# TestNode_V1-pan.net
KiCad netlist of a schematic drawn in EAGLE
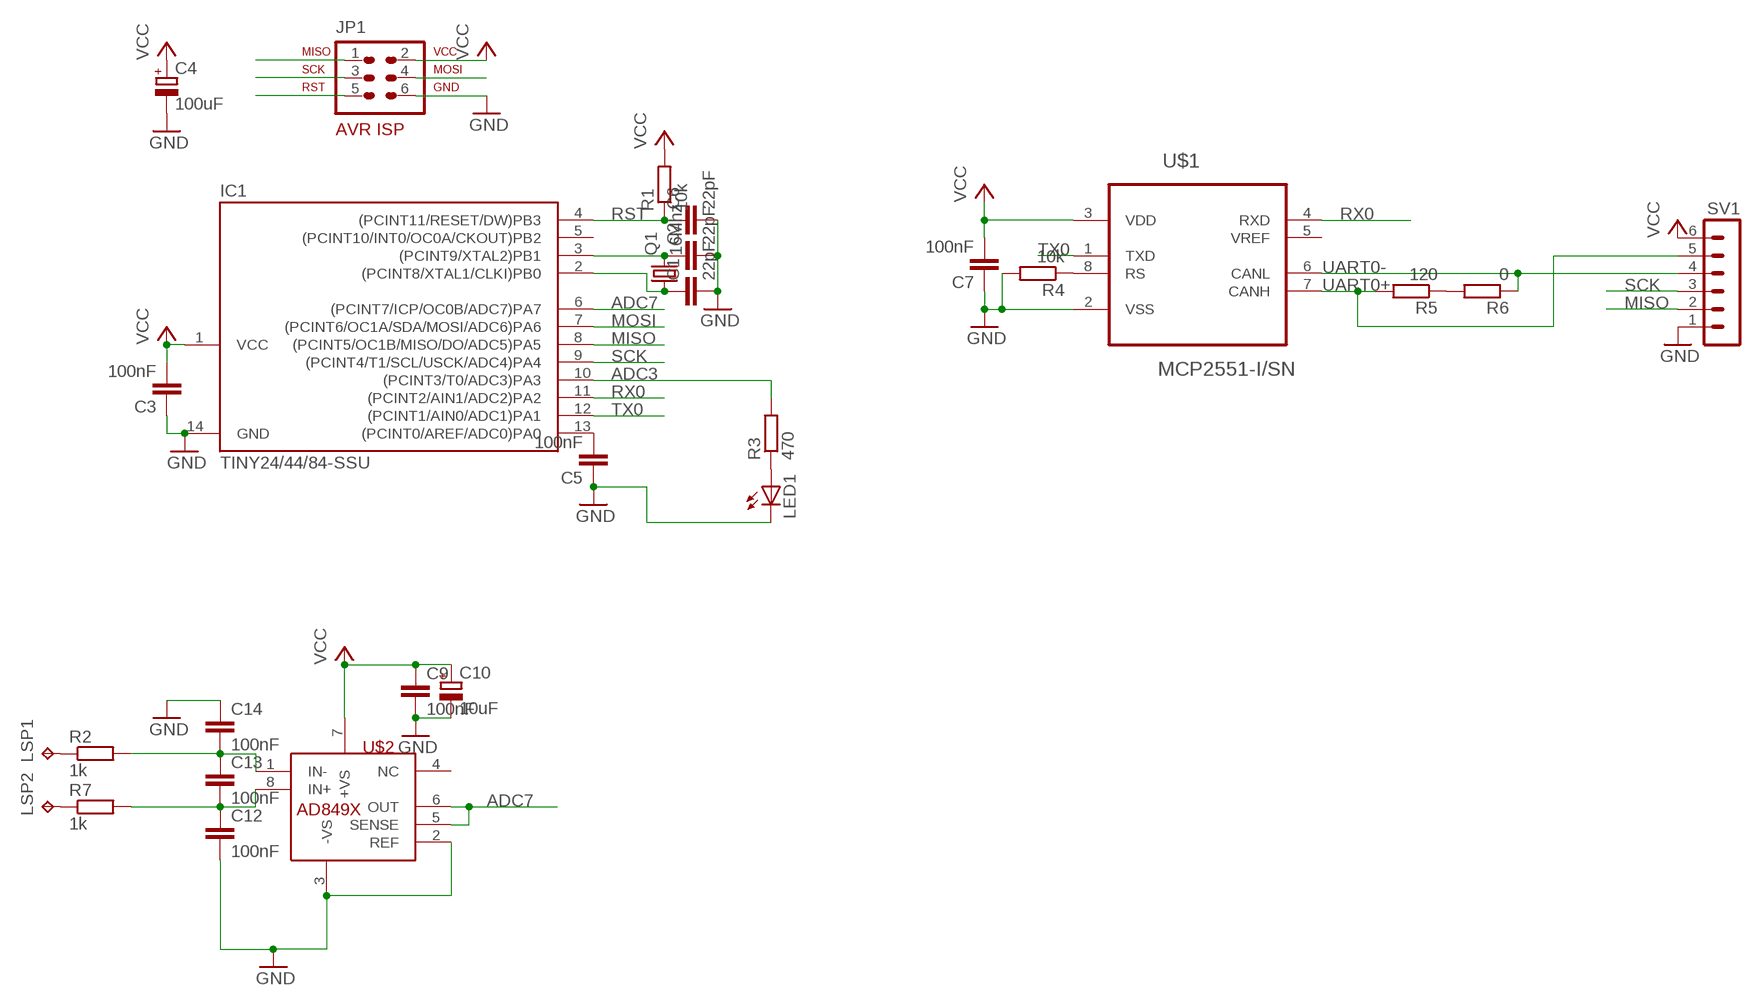
[diagram p0: schematic, sheet 1]

(export (version "E")
  (design (tool "Eeschema 10.0.6"))
  (components
    (comp (ref "C1")
      (value "22pF")
      (footprint "eagle-import:C1206")
      (libsource (lib "eagle-import") (part "C-EUC1206"))
    )
    (comp (ref "C2")
      (value "22pF")
      (footprint "eagle-import:C1206")
      (libsource (lib "eagle-import") (part "C-EUC1206"))
    )
    (comp (ref "C3")
      (value "100nF")
      (footprint "eagle-import:C1206")
      (libsource (lib "eagle-import") (part "C-EUC1206"))
    )
    (comp (ref "C4")
      (value "100uF")
      (footprint "eagle-import:PANASONIC_D")
      (libsource (lib "eagle-import") (part "CPOL-EUD"))
    )
    (comp (ref "C5")
      (value "100nF")
      (footprint "eagle-import:C1206")
      (libsource (lib "eagle-import") (part "C-EUC1206"))
    )
    (comp (ref "C6")
      (value "22pF")
      (footprint "eagle-import:C1206")
      (libsource (lib "eagle-import") (part "C-EUC1206"))
    )
    (comp (ref "C7")
      (value "100nF")
      (footprint "eagle-import:C1206")
      (libsource (lib "eagle-import") (part "C-EUC1206"))
    )
    (comp (ref "C9")
      (value "100nF")
      (footprint "eagle-import:C1206")
      (libsource (lib "eagle-import") (part "C-EUC1206"))
    )
    (comp (ref "C10")
      (value "10uF")
      (footprint "eagle-import:UD-4X5,8_NICHICON")
      (libsource (lib "eagle-import") (part "CPOL-EUUD-4X5,8"))
    )
    (comp (ref "C12")
      (value "100nF")
      (footprint "eagle-import:C0805")
      (libsource (lib "eagle-import") (part "C-EUC0805"))
    )
    (comp (ref "C13")
      (value "100nF")
      (footprint "eagle-import:C0805")
      (libsource (lib "eagle-import") (part "C-EUC0805"))
    )
    (comp (ref "C14")
      (value "100nF")
      (footprint "eagle-import:C0805")
      (libsource (lib "eagle-import") (part "C-EUC0805"))
    )
    (comp (ref "IC1")
      (value "TINY24/44/84-SSU")
      (footprint "eagle-import:SOIC14")
      (libsource (lib "eagle-import") (part "TINY24/44/84-SSU"))
    )
    (comp (ref "JP1")
      (value "AVR-ISP-6VERT")
      (footprint "eagle-import:AVR-ISP-6")
      (libsource (lib "eagle-import") (part "AVR-ISP-6VERT"))
    )
    (comp (ref "LED1")
      (value "LED5MM")
      (footprint "eagle-import:LED5MM")
      (libsource (lib "eagle-import") (part "LED5MM"))
    )
    (comp (ref "LSP1")
      (value "TPTP15R")
      (footprint "eagle-import:TP15R")
      (libsource (lib "eagle-import") (part "TPTP15R"))
    )
    (comp (ref "LSP2")
      (value "TPTP15R")
      (footprint "eagle-import:TP15R")
      (libsource (lib "eagle-import") (part "TPTP15R"))
    )
    (comp (ref "Q1")
      (value "16Mhz")
      (footprint "eagle-import:SM49")
      (libsource (lib "eagle-import") (part "CRYSTALSM49"))
    )
    (comp (ref "R1")
      (value "10k")
      (footprint "eagle-import:R1206")
      (libsource (lib "eagle-import") (part "R-EU_R1206"))
    )
    (comp (ref "R2")
      (value "1k")
      (footprint "eagle-import:R0805")
      (libsource (lib "eagle-import") (part "R-EU_R0805"))
    )
    (comp (ref "R3")
      (value "470")
      (footprint "eagle-import:R1206")
      (libsource (lib "eagle-import") (part "R-EU_R1206"))
    )
    (comp (ref "R4")
      (value "10k")
      (footprint "eagle-import:R1206")
      (libsource (lib "eagle-import") (part "R-EU_R1206"))
    )
    (comp (ref "R5")
      (value "120")
      (footprint "eagle-import:R1206")
      (libsource (lib "eagle-import") (part "R-EU_R1206"))
    )
    (comp (ref "R6")
      (value "0")
      (footprint "eagle-import:R1206")
      (libsource (lib "eagle-import") (part "R-EU_R1206"))
    )
    (comp (ref "R7")
      (value "1k")
      (footprint "eagle-import:R0805")
      (libsource (lib "eagle-import") (part "R-EU_R0805"))
    )
    (comp (ref "SV1")
      (value "MA06-1")
      (footprint "eagle-import:MA06-1")
      (libsource (lib "eagle-import") (part "MA06-1"))
    )
    (comp (ref "U$1")
      (value "MCP2551-I/SN")
      (footprint "eagle-import:SOIC127P600X175-8N")
      (libsource (lib "eagle-import") (part "MCP2551-I/SN"))
    )
    (comp (ref "U$2")
      (value "AD849X")
      (footprint "eagle-import:MSOP8")
      (libsource (lib "eagle-import") (part "AD849X"))
    )
  )
  (nets
    (net (code "1") (name "/ADC3") (class "Default")
      (node (ref "IC1") (pin "10") (pinfunction "(PCINT3/T0/ADC3)PA3_10") (pintype "bidirectional"))
      (node (ref "R3") (pin "2") (pinfunction "2_2") (pintype "passive"))
    )
    (net (code "2") (name "/ADC7") (class "Default")
      (node (ref "IC1") (pin "6") (pinfunction "(PCINT7/ICP/OC0B/ADC7)PA7_6") (pintype "bidirectional"))
      (node (ref "U$2") (pin "5") (pinfunction "SENSE_5") (pintype "input"))
      (node (ref "U$2") (pin "6") (pinfunction "OUT_6") (pintype "output"))
    )
    (net (code "3") (name "/MISO") (class "Default")
      (node (ref "IC1") (pin "8") (pinfunction "(PCINT5/OC1B/MISO/DO/ADC5)PA5_8") (pintype "bidirectional"))
      (node (ref "JP1") (pin "1") (pinfunction "1_1") (pintype "passive"))
      (node (ref "SV1") (pin "2") (pinfunction "2_2") (pintype "passive"))
    )
    (net (code "4") (name "/MOSI") (class "Default")
      (node (ref "IC1") (pin "7") (pinfunction "(PCINT6/OC1A/SDA/MOSI/ADC6)PA6_7") (pintype "bidirectional"))
      (node (ref "JP1") (pin "4") (pinfunction "4_4") (pintype "passive"))
    )
    (net (code "5") (name "/RST") (class "Default")
      (node (ref "C6") (pin "1") (pinfunction "1_1") (pintype "passive"))
      (node (ref "IC1") (pin "4") (pinfunction "(PCINT11/RESET/DW)PB3_4") (pintype "bidirectional"))
      (node (ref "JP1") (pin "5") (pinfunction "5_5") (pintype "passive"))
      (node (ref "R1") (pin "1") (pinfunction "1_1") (pintype "passive"))
    )
    (net (code "6") (name "/RX0") (class "Default")
      (node (ref "IC1") (pin "11") (pinfunction "(PCINT2/AIN1/ADC2)PA2_11") (pintype "bidirectional"))
      (node (ref "U$1") (pin "4") (pinfunction "RXD_4") (pintype "output"))
    )
    (net (code "7") (name "/SCK") (class "Default")
      (node (ref "IC1") (pin "9") (pinfunction "(PCINT4/T1/SCL/USCK/ADC4)PA4_9") (pintype "bidirectional"))
      (node (ref "JP1") (pin "3") (pinfunction "3_3") (pintype "passive"))
      (node (ref "SV1") (pin "3") (pinfunction "3_3") (pintype "passive"))
    )
    (net (code "8") (name "/TX0") (class "Default")
      (node (ref "IC1") (pin "12") (pinfunction "(PCINT1/AIN0/ADC1)PA1_12") (pintype "bidirectional"))
      (node (ref "U$1") (pin "1") (pinfunction "TXD_1") (pintype "input"))
    )
    (net (code "9") (name "/UART0+") (class "Default")
      (node (ref "R5") (pin "2") (pinfunction "2_2") (pintype "passive"))
      (node (ref "SV1") (pin "5") (pinfunction "5_5") (pintype "passive"))
      (node (ref "U$1") (pin "7") (pinfunction "CANH_7") (pintype "bidirectional"))
    )
    (net (code "10") (name "/UART0-") (class "Default")
      (node (ref "R6") (pin "1") (pinfunction "1_1") (pintype "passive"))
      (node (ref "SV1") (pin "4") (pinfunction "4_4") (pintype "passive"))
      (node (ref "U$1") (pin "6") (pinfunction "CANL_6") (pintype "bidirectional"))
    )
    (net (code "11") (name "GND") (class "Default")
      (node (ref "C1") (pin "2") (pinfunction "2_2") (pintype "passive"))
      (node (ref "C10") (pin "-") (pinfunction "-_-") (pintype "passive"))
      (node (ref "C12") (pin "2") (pinfunction "2_2") (pintype "passive"))
      (node (ref "C14") (pin "1") (pinfunction "1_1") (pintype "passive"))
      (node (ref "C2") (pin "2") (pinfunction "2_2") (pintype "passive"))
      (node (ref "C3") (pin "1") (pinfunction "1_1") (pintype "passive"))
      (node (ref "C4") (pin "-") (pinfunction "-_-") (pintype "passive"))
      (node (ref "C5") (pin "1") (pinfunction "1_1") (pintype "passive"))
      (node (ref "C6") (pin "2") (pinfunction "2_2") (pintype "passive"))
      (node (ref "C7") (pin "1") (pinfunction "1_1") (pintype "passive"))
      (node (ref "C9") (pin "2") (pinfunction "2_2") (pintype "passive"))
      (node (ref "IC1") (pin "14") (pinfunction "GND_14") (pintype "power_in"))
      (node (ref "JP1") (pin "6") (pinfunction "6_6") (pintype "passive"))
      (node (ref "LED1") (pin "K") (pinfunction "C_K") (pintype "passive"))
      (node (ref "R4") (pin "2") (pinfunction "2_2") (pintype "passive"))
      (node (ref "SV1") (pin "1") (pinfunction "1_1") (pintype "passive"))
      (node (ref "U$1") (pin "2") (pinfunction "VSS_2") (pintype "passive"))
      (node (ref "U$2") (pin "2") (pinfunction "REF_2") (pintype "input"))
      (node (ref "U$2") (pin "3") (pinfunction "-VS_3") (pintype "power_in"))
    )
    (net (code "12") (name "Net-(IC1-(PCINT0{slash}AREF{slash}ADC0)PA0)") (class "Default")
      (node (ref "C5") (pin "2") (pinfunction "2_2") (pintype "passive"))
      (node (ref "IC1") (pin "13") (pinfunction "(PCINT0/AREF/ADC0)PA0_13") (pintype "bidirectional"))
    )
    (net (code "13") (name "Net-(IC1-(PCINT8{slash}XTAL1{slash}CLKI)PB0)") (class "Default")
      (node (ref "C1") (pin "1") (pinfunction "1_1") (pintype "passive"))
      (node (ref "IC1") (pin "2") (pinfunction "(PCINT8/XTAL1/CLKI)PB0_2") (pintype "bidirectional"))
      (node (ref "Q1") (pin "1") (pinfunction "1_1") (pintype "passive"))
    )
    (net (code "14") (name "Net-(IC1-(PCINT9{slash}XTAL2)PB1)") (class "Default")
      (node (ref "C2") (pin "1") (pinfunction "1_1") (pintype "passive"))
      (node (ref "IC1") (pin "3") (pinfunction "(PCINT9/XTAL2)PB1_3") (pintype "bidirectional"))
      (node (ref "Q1") (pin "2") (pinfunction "2_2") (pintype "passive"))
    )
    (net (code "15") (name "Net-(LED1-PadA)") (class "Default")
      (node (ref "LED1") (pin "A") (pinfunction "A_A") (pintype "passive"))
      (node (ref "R3") (pin "1") (pinfunction "1_1") (pintype "passive"))
    )
    (net (code "16") (name "Net-(LSP1-PadTP)") (class "Default")
      (node (ref "LSP1") (pin "TP") (pinfunction "TP_TP") (pintype "input"))
      (node (ref "R2") (pin "1") (pinfunction "1_1") (pintype "passive"))
    )
    (net (code "17") (name "Net-(LSP2-PadTP)") (class "Default")
      (node (ref "LSP2") (pin "TP") (pinfunction "TP_TP") (pintype "input"))
      (node (ref "R7") (pin "1") (pinfunction "1_1") (pintype "passive"))
    )
    (net (code "18") (name "Net-(R5-Pad1)") (class "Default")
      (node (ref "R5") (pin "1") (pinfunction "1_1") (pintype "passive"))
      (node (ref "R6") (pin "2") (pinfunction "2_2") (pintype "passive"))
    )
    (net (code "19") (name "Net-(U$1-RS)") (class "Default")
      (node (ref "R4") (pin "1") (pinfunction "1_1") (pintype "passive"))
      (node (ref "U$1") (pin "8") (pinfunction "RS_8") (pintype "input"))
    )
    (net (code "20") (name "Net-(U$2-IN+)") (class "Default")
      (node (ref "C12") (pin "1") (pinfunction "1_1") (pintype "passive"))
      (node (ref "C13") (pin "2") (pinfunction "2_2") (pintype "passive"))
      (node (ref "R7") (pin "2") (pinfunction "2_2") (pintype "passive"))
      (node (ref "U$2") (pin "8") (pinfunction "IN+_8") (pintype "input"))
    )
    (net (code "21") (name "Net-(U$2-IN-)") (class "Default")
      (node (ref "C13") (pin "1") (pinfunction "1_1") (pintype "passive"))
      (node (ref "C14") (pin "2") (pinfunction "2_2") (pintype "passive"))
      (node (ref "R2") (pin "2") (pinfunction "2_2") (pintype "passive"))
      (node (ref "U$2") (pin "1") (pinfunction "IN-_1") (pintype "input"))
    )
    (net (code "22") (name "VCC") (class "Default")
      (node (ref "C10") (pin "+") (pinfunction "+_+") (pintype "passive"))
      (node (ref "C3") (pin "2") (pinfunction "2_2") (pintype "passive"))
      (node (ref "C4") (pin "+") (pinfunction "+_+") (pintype "passive"))
      (node (ref "C7") (pin "2") (pinfunction "2_2") (pintype "passive"))
      (node (ref "C9") (pin "1") (pinfunction "1_1") (pintype "passive"))
      (node (ref "IC1") (pin "1") (pinfunction "VCC_1") (pintype "power_in"))
      (node (ref "JP1") (pin "2") (pinfunction "2_2") (pintype "passive"))
      (node (ref "R1") (pin "2") (pinfunction "2_2") (pintype "passive"))
      (node (ref "SV1") (pin "6") (pinfunction "6_6") (pintype "passive"))
      (node (ref "U$1") (pin "3") (pinfunction "VDD_3") (pintype "power_in"))
      (node (ref "U$2") (pin "7") (pinfunction "+VS_7") (pintype "power_in"))
    )
    (net (code "23") (name "unconnected-(IC1-(PCINT10{slash}INT0{slash}OC0A{slash}CKOUT)PB2-Pad5)") (class "Default")
      (node (ref "IC1") (pin "5") (pinfunction "(PCINT10/INT0/OC0A/CKOUT)PB2_5") (pintype "bidirectional"))
    )
    (net (code "24") (name "unconnected-(U$1-VREF-Pad5)") (class "Default")
      (node (ref "U$1") (pin "5") (pinfunction "VREF_5") (pintype "output"))
    )
    (net (code "25") (name "unconnected-(U$2-NC-Pad4)") (class "Default")
      (node (ref "U$2") (pin "4") (pinfunction "NC_4") (pintype "no_connect"))
    )
  )
)
